# OLED.net
KiCad netlist of a schematic drawn in Altium Designer
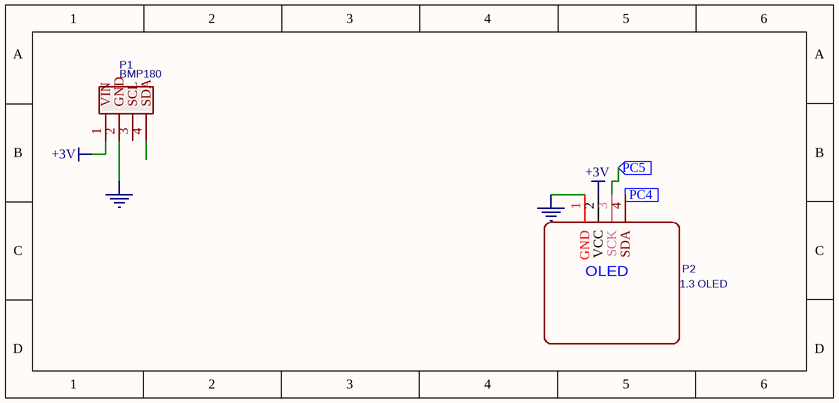
[diagram p0: OLED.schdoc]

(export (version "E")
  (design (tool "Eeschema 10.0.6"))
  (components
    (comp (ref "P1")
      (value "BMP180")
      (fields
        (field (name "BOM_MANUFACTURER PART") "Headers  Pins 1*4P")
        (field (name "BOM_SUPPLIER PART") "C59481")
      )
      (libsource (lib "altium-import") (part "root_1_BMP180_"))
    )
    (comp (ref "P2")
      (value "1.3 OLED")
      (fields (field (name "BOM_MANUFACTURER PART") "?"))
      (libsource (lib "altium-import") (part "root_0_1.3 OLED_"))
    )
  )
  (nets
    (net (code "1") (name "+3V") (class "Default")
      (node (ref "P1") (pin "1") (pinfunction "VIN_1") (pintype "passive"))
      (node (ref "P2") (pin "2") (pinfunction "VCC_2") (pintype "passive"))
    )
    (net (code "2") (name "/PC4") (class "Default")
      (node (ref "P2") (pin "4") (pinfunction "SDA_4") (pintype "passive"))
    )
    (net (code "3") (name "/PC5") (class "Default")
      (node (ref "P2") (pin "3") (pinfunction "SCK_3") (pintype "passive"))
    )
    (net (code "4") (name "GND") (class "Default")
      (node (ref "P1") (pin "2") (pinfunction "GND_2") (pintype "passive"))
      (node (ref "P2") (pin "1") (pinfunction "GND_1") (pintype "passive"))
    )
    (net (code "5") (name "unconnected-(P1-SCL-Pad3)") (class "Default")
      (node (ref "P1") (pin "3") (pinfunction "SCL_3") (pintype "passive"))
    )
    (net (code "6") (name "unconnected-(P1-SDA-Pad4)") (class "Default")
      (node (ref "P1") (pin "4") (pinfunction "SDA_4") (pintype "passive"))
    )
  )
)
